# LBS-Simpleceiver_Audio_Pre-Amp_and_Amp_S.net
KiCad netlist of a schematic drawn in EAGLE
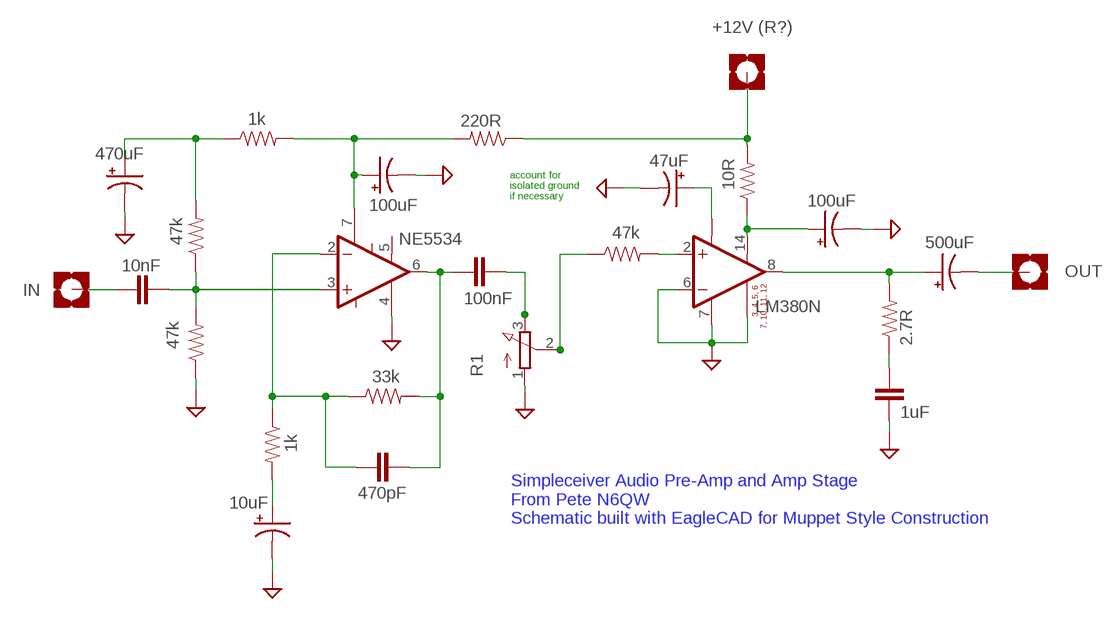
[diagram p0: schematic, sheet 1]

(export (version "E")
  (design (tool "Eeschema 10.0.6"))
  (components
    (comp (ref "C1")
      (value "470uF")
      (footprint "eagle-import:CAP-POLARIZED")
      (libsource (lib "eagle-import") (part "CAP-POLARIZED-RADIAL-2.5MM-25V-20%"))
    )
    (comp (ref "C2")
      (value "100uF")
      (footprint "eagle-import:CAP-POLARIZED")
      (libsource (lib "eagle-import") (part "CAP-POLARIZED-RADIAL-2.5MM-25V-20%"))
    )
    (comp (ref "C3")
      (value "500uF")
      (footprint "eagle-import:CAP-POLARIZED")
      (libsource (lib "eagle-import") (part "CAP-POLARIZED-RADIAL-2.5MM-25V-20%"))
    )
    (comp (ref "C4")
      (value "47uF")
      (footprint "eagle-import:CAP-POLARIZED")
      (libsource (lib "eagle-import") (part "CAP-POLARIZED-RADIAL-2.5MM-25V-20%"))
    )
    (comp (ref "C5")
      (value "10uF")
      (footprint "eagle-import:CAP-POLARIZED")
      (libsource (lib "eagle-import") (part "CAP-POLARIZED-RADIAL-2.5MM-25V-20%"))
    )
    (comp (ref "C6")
      (value "100uF")
      (footprint "eagle-import:CAP-POLARIZED")
      (libsource (lib "eagle-import") (part "CAP-POLARIZED-RADIAL-2.5MM-25V-20%"))
    )
    (comp (ref "C7")
      (value "10nF")
      (footprint "eagle-import:CAP-MEDIUM-MUPPET")
      (libsource (lib "eagle-import") (part "CAP-MEDIUM-MUPPET"))
    )
    (comp (ref "C8")
      (value "100nF")
      (footprint "eagle-import:CAP-MEDIUM-MUPPET")
      (libsource (lib "eagle-import") (part "CAP-MEDIUM-MUPPET"))
    )
    (comp (ref "C9")
      (value "1uF")
      (footprint "eagle-import:CAP-MEDIUM-MUPPET")
      (libsource (lib "eagle-import") (part "CAP-MEDIUM-MUPPET"))
    )
    (comp (ref "C10")
      (value "470pF")
      (footprint "eagle-import:CAP-MEDIUM-MUPPET")
      (libsource (lib "eagle-import") (part "CAP-MEDIUM-MUPPET"))
    )
    (comp (ref "H1")
      (value "IN")
      (footprint "eagle-import:PAD-SQUARE")
      (libsource (lib "eagle-import") (part "MOUNT-PAD-SQUARE4.5"))
    )
    (comp (ref "H2")
      (value "OUT")
      (footprint "eagle-import:PAD-SQUARE")
      (libsource (lib "eagle-import") (part "MOUNT-PAD-SQUARE4.5"))
    )
    (comp (ref "H3")
      (value "+12V (R?)")
      (footprint "eagle-import:PAD-SQUARE")
      (libsource (lib "eagle-import") (part "MOUNT-PAD-SQUARE4.5"))
    )
    (comp (ref "IC1")
      (value "NE5534")
      (footprint "eagle-import:DIL08")
      (libsource (lib "eagle-import") (part "NE5534-OP-AMPDIL8"))
    )
    (comp (ref "R1")
      (value "POTENTIOMETER")
      (footprint "eagle-import:POTENTIOMETER")
      (libsource (lib "eagle-import") (part "POTENTIOMETER"))
    )
    (comp (ref "R2")
      (value "47k")
      (footprint "eagle-import:RESITOR-MUPPET")
      (libsource (lib "eagle-import") (part "RESISTOR-MUPPETMEDIUM-RESISTOR-PADS"))
    )
    (comp (ref "R3")
      (value "47k")
      (footprint "eagle-import:RESITOR-MUPPET")
      (libsource (lib "eagle-import") (part "RESISTOR-MUPPETMEDIUM-RESISTOR-PADS"))
    )
    (comp (ref "R4")
      (value "1k")
      (footprint "eagle-import:RESITOR-MUPPET")
      (libsource (lib "eagle-import") (part "RESISTOR-MUPPETMEDIUM-RESISTOR-PADS"))
    )
    (comp (ref "R5")
      (value "33k")
      (footprint "eagle-import:RESITOR-MUPPET")
      (libsource (lib "eagle-import") (part "RESISTOR-MUPPETMEDIUM-RESISTOR-PADS"))
    )
    (comp (ref "R8")
      (value "220R")
      (footprint "eagle-import:RESITOR-MUPPET")
      (libsource (lib "eagle-import") (part "RESISTOR-MUPPETMEDIUM-RESISTOR-PADS"))
    )
    (comp (ref "R9")
      (value "2.7R")
      (footprint "eagle-import:RESITOR-MUPPET")
      (libsource (lib "eagle-import") (part "RESISTOR-MUPPETMEDIUM-RESISTOR-PADS"))
    )
    (comp (ref "U$4")
      (value "1k")
      (footprint "eagle-import:RESITOR-MUPPET")
      (libsource (lib "eagle-import") (part "RESISTOR-MUPPETMEDIUM-RESISTOR-PADS"))
    )
    (comp (ref "U$6")
      (value "47k")
      (footprint "eagle-import:RESITOR-MUPPET")
      (libsource (lib "eagle-import") (part "RESISTOR-MUPPETMEDIUM-RESISTOR-PADS"))
    )
    (comp (ref "U$7")
      (value "10R")
      (footprint "eagle-import:RESITOR-MUPPET")
      (libsource (lib "eagle-import") (part "RESISTOR-MUPPETMEDIUM-RESISTOR-PADS"))
    )
    (comp (ref "U1")
      (value "LM380N")
      (footprint "eagle-import:DIL14")
      (libsource (lib "eagle-import") (part "LM380N-AUDIO-PWR-AMPDIL14"))
    )
  )
  (nets
    (net (code "1") (name "GND") (class "Default")
      (node (ref "C1") (pin "2") (pinfunction "-_2") (pintype "passive"))
      (node (ref "C2") (pin "2") (pinfunction "-_2") (pintype "passive"))
      (node (ref "C4") (pin "2") (pinfunction "-_2") (pintype "passive"))
      (node (ref "C5") (pin "2") (pinfunction "-_2") (pintype "passive"))
      (node (ref "C6") (pin "2") (pinfunction "-_2") (pintype "passive"))
      (node (ref "C9") (pin "2") (pinfunction "2_2") (pintype "passive"))
      (node (ref "IC1") (pin "4") (pinfunction "VCC-GND_4") (pintype "power_in"))
      (node (ref "R1") (pin "1") (pinfunction "A_1") (pintype "passive"))
      (node (ref "R3") (pin "P$1") (pinfunction "1_P$1") (pintype "passive"))
      (node (ref "U1") (pin "10") (pinfunction "GND_10") (pintype "passive"))
      (node (ref "U1") (pin "11") (pinfunction "GND_11") (pintype "passive"))
      (node (ref "U1") (pin "12") (pinfunction "GND_12") (pintype "passive"))
      (node (ref "U1") (pin "3") (pinfunction "GND_3") (pintype "passive"))
      (node (ref "U1") (pin "4") (pinfunction "GND_4") (pintype "passive"))
      (node (ref "U1") (pin "5") (pinfunction "GND_5") (pintype "passive"))
      (node (ref "U1") (pin "6") (pinfunction "-IN_6") (pintype "input"))
      (node (ref "U1") (pin "7") (pinfunction "GND1_7") (pintype "passive"))
    )
    (net (code "2") (name "Net-(C1-+)") (class "Default")
      (node (ref "C1") (pin "1") (pinfunction "+_1") (pintype "passive"))
      (node (ref "R2") (pin "P$2") (pinfunction "2_P$2") (pintype "passive"))
      (node (ref "R4") (pin "P$1") (pinfunction "1_P$1") (pintype "passive"))
    )
    (net (code "3") (name "Net-(C2-+)") (class "Default")
      (node (ref "C2") (pin "1") (pinfunction "+_1") (pintype "passive"))
      (node (ref "U$7") (pin "P$1") (pinfunction "1_P$1") (pintype "passive"))
      (node (ref "U1") (pin "14") (pinfunction "V-SIG_14") (pintype "bidirectional"))
    )
    (net (code "4") (name "Net-(C3-+)") (class "Default")
      (node (ref "C3") (pin "1") (pinfunction "+_1") (pintype "passive"))
      (node (ref "R9") (pin "P$2") (pinfunction "2_P$2") (pintype "passive"))
      (node (ref "U1") (pin "8") (pinfunction "GAIN_8") (pintype "output"))
    )
    (net (code "5") (name "Net-(C3--)") (class "Default")
      (node (ref "C3") (pin "2") (pinfunction "-_2") (pintype "passive"))
      (node (ref "H2") (pin "PAD") (pinfunction "MOUNT_PAD") (pintype "passive"))
    )
    (net (code "6") (name "Net-(C4-+)") (class "Default")
      (node (ref "C4") (pin "1") (pinfunction "+_1") (pintype "passive"))
      (node (ref "U1") (pin "1") (pinfunction "BYPASS_1") (pintype "passive"))
    )
    (net (code "7") (name "Net-(C5-+)") (class "Default")
      (node (ref "C5") (pin "1") (pinfunction "+_1") (pintype "passive"))
      (node (ref "U$4") (pin "P$2") (pinfunction "2_P$2") (pintype "passive"))
    )
    (net (code "8") (name "Net-(C6-+)") (class "Default")
      (node (ref "C6") (pin "1") (pinfunction "+_1") (pintype "passive"))
      (node (ref "IC1") (pin "7") (pinfunction "VCC+_7") (pintype "power_in"))
      (node (ref "R4") (pin "P$2") (pinfunction "2_P$2") (pintype "passive"))
      (node (ref "R8") (pin "P$2") (pinfunction "2_P$2") (pintype "passive"))
    )
    (net (code "9") (name "Net-(H1-MOUNT)") (class "Default")
      (node (ref "C7") (pin "1") (pinfunction "1_1") (pintype "passive"))
      (node (ref "H1") (pin "PAD") (pinfunction "MOUNT_PAD") (pintype "passive"))
    )
    (net (code "10") (name "Net-(H3-MOUNT)") (class "Default")
      (node (ref "H3") (pin "PAD") (pinfunction "MOUNT_PAD") (pintype "passive"))
      (node (ref "R8") (pin "P$1") (pinfunction "1_P$1") (pintype "passive"))
      (node (ref "U$7") (pin "P$2") (pinfunction "2_P$2") (pintype "passive"))
    )
    (net (code "11") (name "Net-(IC1-+IN)") (class "Default")
      (node (ref "C7") (pin "2") (pinfunction "2_2") (pintype "passive"))
      (node (ref "IC1") (pin "3") (pinfunction "+IN_3") (pintype "input"))
      (node (ref "R2") (pin "P$1") (pinfunction "1_P$1") (pintype "passive"))
      (node (ref "R3") (pin "P$2") (pinfunction "2_P$2") (pintype "passive"))
    )
    (net (code "12") (name "Net-(IC1--IN)") (class "Default")
      (node (ref "C10") (pin "2") (pinfunction "2_2") (pintype "passive"))
      (node (ref "IC1") (pin "2") (pinfunction "-IN_2") (pintype "input"))
      (node (ref "R5") (pin "P$1") (pinfunction "1_P$1") (pintype "passive"))
      (node (ref "U$4") (pin "P$1") (pinfunction "1_P$1") (pintype "passive"))
    )
    (net (code "13") (name "Net-(IC1-OUT)") (class "Default")
      (node (ref "C10") (pin "1") (pinfunction "1_1") (pintype "passive"))
      (node (ref "C8") (pin "2") (pinfunction "2_2") (pintype "passive"))
      (node (ref "IC1") (pin "6") (pinfunction "OUT_6") (pintype "output"))
      (node (ref "R5") (pin "P$2") (pinfunction "2_P$2") (pintype "passive"))
    )
    (net (code "14") (name "Net-(R1-E)") (class "Default")
      (node (ref "C8") (pin "1") (pinfunction "1_1") (pintype "passive"))
      (node (ref "R1") (pin "3") (pinfunction "E_3") (pintype "passive"))
    )
    (net (code "15") (name "Net-(R1-S)") (class "Default")
      (node (ref "R1") (pin "2") (pinfunction "S_2") (pintype "passive"))
      (node (ref "U$6") (pin "P$1") (pinfunction "1_P$1") (pintype "passive"))
    )
    (net (code "16") (name "Net-(R9-1)") (class "Default")
      (node (ref "C9") (pin "1") (pinfunction "1_1") (pintype "passive"))
      (node (ref "R9") (pin "P$1") (pinfunction "1_P$1") (pintype "passive"))
    )
    (net (code "17") (name "Net-(U$6-2)") (class "Default")
      (node (ref "U$6") (pin "P$2") (pinfunction "2_P$2") (pintype "passive"))
      (node (ref "U1") (pin "2") (pinfunction "+IN_2") (pintype "input"))
    )
    (net (code "18") (name "unconnected-(IC1-BALANCE-Pad1)") (class "Default")
      (node (ref "IC1") (pin "1") (pinfunction "BALANCE_1") (pintype "passive"))
    )
    (net (code "19") (name "unconnected-(IC1-COMP-Pad5)") (class "Default")
      (node (ref "IC1") (pin "5") (pinfunction "COMP_5") (pintype "passive"))
    )
    (net (code "20") (name "unconnected-(IC1-COMP{slash}BAL-Pad8)") (class "Default")
      (node (ref "IC1") (pin "8") (pinfunction "COMP/BAL_8") (pintype "passive"))
    )
  )
)
